# dashboard.net
KiCad netlist of a schematic drawn in EAGLE
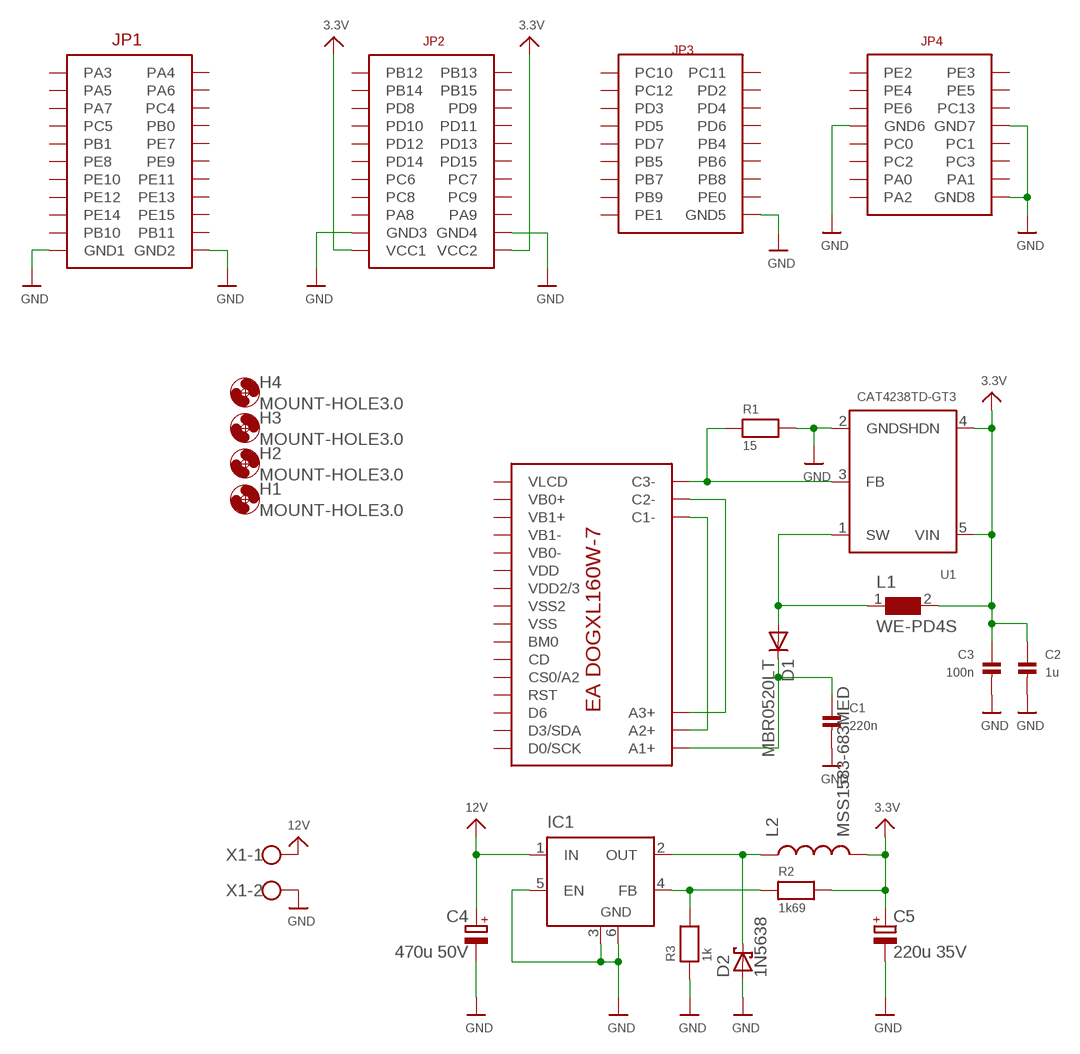
[diagram p0: schematic, sheet 1]

(export (version "E")
  (design (tool "Eeschema 10.0.6"))
  (components
    (comp (ref "C1")
      (value "220n")
      (footprint "eagle-import:_0805")
      (libsource (lib "eagle-import") (part "CAP_CERAMIC_0805"))
    )
    (comp (ref "C2")
      (value "1u")
      (footprint "eagle-import:_0805")
      (libsource (lib "eagle-import") (part "CAP_CERAMIC_0805"))
    )
    (comp (ref "C3")
      (value "100n")
      (footprint "eagle-import:_0603")
      (libsource (lib "eagle-import") (part "CAP_CERAMIC_0603"))
    )
    (comp (ref "C4")
      (value "470u 50V")
      (footprint "eagle-import:E5-13")
      (libsource (lib "eagle-import") (part "CPOL-EUE5-13"))
    )
    (comp (ref "C5")
      (value "220u 35V")
      (footprint "eagle-import:E3,5-8")
      (libsource (lib "eagle-import") (part "CPOL-EUE3.5-8"))
    )
    (comp (ref "D1")
      (value "MBR0520LT")
      (footprint "eagle-import:SOD123")
      (libsource (lib "eagle-import") (part "MBR0520LT"))
    )
    (comp (ref "D2")
      (value "1N5638")
      (footprint "eagle-import:DO13M")
      (libsource (lib "eagle-import") (part "1N5638"))
    )
    (comp (ref "H1")
      (value "MOUNT-HOLE3.0")
      (footprint "eagle-import:3,0")
      (libsource (lib "eagle-import") (part "MOUNT-HOLE3.0"))
    )
    (comp (ref "H2")
      (value "MOUNT-HOLE3.0")
      (footprint "eagle-import:3,0")
      (libsource (lib "eagle-import") (part "MOUNT-HOLE3.0"))
    )
    (comp (ref "H3")
      (value "MOUNT-HOLE3.0")
      (footprint "eagle-import:3,0")
      (libsource (lib "eagle-import") (part "MOUNT-HOLE3.0"))
    )
    (comp (ref "H4")
      (value "MOUNT-HOLE3.0")
      (footprint "eagle-import:3,0")
      (libsource (lib "eagle-import") (part "MOUNT-HOLE3.0"))
    )
    (comp (ref "IC1")
      (value "LM2596S")
      (footprint "eagle-import:TO263-5")
      (libsource (lib "eagle-import") (part "LM2596S"))
    )
    (comp (ref "L1")
      (value "WE-PD4S")
      (footprint "eagle-import:S")
      (fields (field (name "MPN") "7445501"))
      (libsource (lib "eagle-import") (part "WE-PD4_S-7445501"))
    )
    (comp (ref "L2")
      (value "MSS1583-683MED")
      (footprint "eagle-import:CDRH125")
      (libsource (lib "eagle-import") (part "INDUCTORPWR"))
    )
    (comp (ref "R1")
      (value "15")
      (footprint "eagle-import:_0603")
      (libsource (lib "eagle-import") (part "RESISTOR_0603"))
    )
    (comp (ref "R2")
      (value "1k69")
      (footprint "eagle-import:_0603")
      (libsource (lib "eagle-import") (part "RESISTOR_0603"))
    )
    (comp (ref "R3")
      (value "1k")
      (footprint "eagle-import:_0603")
      (libsource (lib "eagle-import") (part "RESISTOR_0603"))
    )
    (comp (ref "U$1")
      (value "CPU-BOARD")
      (footprint "eagle-import:CPU-BOARD-JP1")
      (libsource (lib "eagle-import") (part "CPU-BOARD"))
    )
    (comp (ref "U$10")
      (value "EA-DOGXL160W-7")
      (footprint "eagle-import:EA-DOGXL160W-7")
      (libsource (lib "eagle-import") (part "EA-DOGXL160W-7"))
    )
    (comp (ref "U1")
      (value "CAT4238TD-GT3")
      (footprint "eagle-import:SOT23-5")
      (libsource (lib "eagle-import") (part "FAN5331"))
    )
    (comp (ref "X1")
      (value "W237-102")
      (footprint "eagle-import:W237-102")
      (fields (field (name "MPN") "237-102"))
      (libsource (lib "eagle-import") (part "W237-102"))
    )
  )
  (nets
    (net (code "1") (name "3.3V") (class "Default")
      (node (ref "C2") (pin "1") (pinfunction "P$1_1") (pintype "passive"))
      (node (ref "C3") (pin "1") (pinfunction "P$1_1") (pintype "passive"))
      (node (ref "C5") (pin "+") (pinfunction "+_+") (pintype "passive"))
      (node (ref "L1") (pin "2") (pinfunction "2_2") (pintype "passive"))
      (node (ref "L2") (pin "2") (pinfunction "2_2") (pintype "passive"))
      (node (ref "R2") (pin "2") (pinfunction "2_2") (pintype "passive"))
      (node (ref "U$1") (pin "P$43") (pinfunction "VCC1_P$43") (pintype "bidirectional"))
      (node (ref "U$1") (pin "P$44") (pinfunction "VCC2_P$44") (pintype "bidirectional"))
      (node (ref "U1") (pin "4") (pinfunction "SHDN_4") (pintype "bidirectional"))
      (node (ref "U1") (pin "5") (pinfunction "VIN_5") (pintype "bidirectional"))
    )
    (net (code "2") (name "12V") (class "Default")
      (node (ref "C4") (pin "+") (pinfunction "+_+") (pintype "passive"))
      (node (ref "IC1") (pin "1") (pinfunction "IN_1") (pintype "input"))
      (node (ref "X1") (pin "1") (pinfunction "KL_1") (pintype "passive"))
    )
    (net (code "3") (name "GND") (class "Default")
      (node (ref "C1") (pin "2") (pinfunction "P$2_2") (pintype "passive"))
      (node (ref "C2") (pin "2") (pinfunction "P$2_2") (pintype "passive"))
      (node (ref "C3") (pin "2") (pinfunction "P$2_2") (pintype "passive"))
      (node (ref "C4") (pin "-") (pinfunction "-_-") (pintype "passive"))
      (node (ref "C5") (pin "-") (pinfunction "-_-") (pintype "passive"))
      (node (ref "D2") (pin "A") (pinfunction "A_A") (pintype "passive"))
      (node (ref "IC1") (pin "3") (pinfunction "GND_3") (pintype "power_in"))
      (node (ref "IC1") (pin "5") (pinfunction "EN_5") (pintype "input"))
      (node (ref "IC1") (pin "6") (pinfunction "GND_6") (pintype "power_in"))
      (node (ref "R1") (pin "2") (pinfunction "2_2") (pintype "passive"))
      (node (ref "R3") (pin "1") (pinfunction "1_1") (pintype "passive"))
      (node (ref "U$1") (pin "P$21") (pinfunction "GND1_P$21") (pintype "bidirectional"))
      (node (ref "U$1") (pin "P$22") (pinfunction "GND2_P$22") (pintype "bidirectional"))
      (node (ref "U$1") (pin "P$41") (pinfunction "GND3_P$41") (pintype "bidirectional"))
      (node (ref "U$1") (pin "P$42") (pinfunction "GND4_P$42") (pintype "bidirectional"))
      (node (ref "U$1") (pin "P$62") (pinfunction "GND5_P$62") (pintype "bidirectional"))
      (node (ref "U$1") (pin "P$69") (pinfunction "GND6_P$69") (pintype "bidirectional"))
      (node (ref "U$1") (pin "P$70") (pinfunction "GND7_P$70") (pintype "bidirectional"))
      (node (ref "U$1") (pin "P$78") (pinfunction "GND8_P$78") (pintype "bidirectional"))
      (node (ref "U1") (pin "2") (pinfunction "GND_2") (pintype "bidirectional"))
      (node (ref "X1") (pin "2") (pinfunction "KL_2") (pintype "passive"))
    )
    (net (code "4") (name "Net-(C1-P$1)") (class "Default")
      (node (ref "C1") (pin "1") (pinfunction "P$1_1") (pintype "passive"))
      (node (ref "D1") (pin "C") (pinfunction "C_C") (pintype "passive"))
      (node (ref "U$10") (pin "P$1") (pinfunction "A1+_P$1") (pintype "bidirectional"))
    )
    (net (code "5") (name "Net-(IC1-FB)") (class "Default")
      (node (ref "IC1") (pin "4") (pinfunction "FB_4") (pintype "input"))
      (node (ref "R2") (pin "1") (pinfunction "1_1") (pintype "passive"))
      (node (ref "R3") (pin "2") (pinfunction "2_2") (pintype "passive"))
    )
    (net (code "6") (name "Net-(IC1-OUT)") (class "Default")
      (node (ref "D2") (pin "C") (pinfunction "C_C") (pintype "passive"))
      (node (ref "IC1") (pin "2") (pinfunction "OUT_2") (pintype "output"))
      (node (ref "L2") (pin "1") (pinfunction "1_1") (pintype "passive"))
    )
    (net (code "7") (name "Net-(U$10-A2+)") (class "Default")
      (node (ref "U$10") (pin "P$14") (pinfunction "C1-_P$14") (pintype "bidirectional"))
      (node (ref "U$10") (pin "P$2") (pinfunction "A2+_P$2") (pintype "bidirectional"))
    )
    (net (code "8") (name "Net-(U$10-A3+)") (class "Default")
      (node (ref "U$10") (pin "P$15") (pinfunction "C2-_P$15") (pintype "bidirectional"))
      (node (ref "U$10") (pin "P$3") (pinfunction "A3+_P$3") (pintype "bidirectional"))
    )
    (net (code "9") (name "Net-(U$10-C3-)") (class "Default")
      (node (ref "R1") (pin "1") (pinfunction "1_1") (pintype "passive"))
      (node (ref "U$10") (pin "P$16") (pinfunction "C3-_P$16") (pintype "bidirectional"))
      (node (ref "U1") (pin "3") (pinfunction "FB_3") (pintype "bidirectional"))
    )
    (net (code "10") (name "Net-(U1-SW)") (class "Default")
      (node (ref "D1") (pin "A") (pinfunction "A_A") (pintype "passive"))
      (node (ref "L1") (pin "1") (pinfunction "1_1") (pintype "passive"))
      (node (ref "U1") (pin "1") (pinfunction "SW_1") (pintype "bidirectional"))
    )
    (net (code "11") (name "unconnected-(U$1A-PA3-PadP$1)") (class "Default")
      (node (ref "U$1") (pin "P$1") (pinfunction "PA3_P$1") (pintype "bidirectional"))
    )
    (net (code "12") (name "unconnected-(U$1A-PA4-PadP$2)") (class "Default")
      (node (ref "U$1") (pin "P$2") (pinfunction "PA4_P$2") (pintype "bidirectional"))
    )
    (net (code "13") (name "unconnected-(U$1A-PA5-PadP$3)") (class "Default")
      (node (ref "U$1") (pin "P$3") (pinfunction "PA5_P$3") (pintype "bidirectional"))
    )
    (net (code "14") (name "unconnected-(U$1A-PA6-PadP$4)") (class "Default")
      (node (ref "U$1") (pin "P$4") (pinfunction "PA6_P$4") (pintype "bidirectional"))
    )
    (net (code "15") (name "unconnected-(U$1A-PA7-PadP$5)") (class "Default")
      (node (ref "U$1") (pin "P$5") (pinfunction "PA7_P$5") (pintype "bidirectional"))
    )
    (net (code "16") (name "unconnected-(U$1A-PB0-PadP$8)") (class "Default")
      (node (ref "U$1") (pin "P$8") (pinfunction "PB0_P$8") (pintype "bidirectional"))
    )
    (net (code "17") (name "unconnected-(U$1A-PB1-PadP$9)") (class "Default")
      (node (ref "U$1") (pin "P$9") (pinfunction "PB1_P$9") (pintype "bidirectional"))
    )
    (net (code "18") (name "unconnected-(U$1A-PB10-PadP$19)") (class "Default")
      (node (ref "U$1") (pin "P$19") (pinfunction "PB10_P$19") (pintype "bidirectional"))
    )
    (net (code "19") (name "unconnected-(U$1A-PB11-PadP$20)") (class "Default")
      (node (ref "U$1") (pin "P$20") (pinfunction "PB11_P$20") (pintype "bidirectional"))
    )
    (net (code "20") (name "unconnected-(U$1A-PC4-PadP$6)") (class "Default")
      (node (ref "U$1") (pin "P$6") (pinfunction "PC4_P$6") (pintype "bidirectional"))
    )
    (net (code "21") (name "unconnected-(U$1A-PC5-PadP$7)") (class "Default")
      (node (ref "U$1") (pin "P$7") (pinfunction "PC5_P$7") (pintype "bidirectional"))
    )
    (net (code "22") (name "unconnected-(U$1A-PE7-PadP$10)") (class "Default")
      (node (ref "U$1") (pin "P$10") (pinfunction "PE7_P$10") (pintype "bidirectional"))
    )
    (net (code "23") (name "unconnected-(U$1A-PE8-PadP$11)") (class "Default")
      (node (ref "U$1") (pin "P$11") (pinfunction "PE8_P$11") (pintype "bidirectional"))
    )
    (net (code "24") (name "unconnected-(U$1A-PE9-PadP$12)") (class "Default")
      (node (ref "U$1") (pin "P$12") (pinfunction "PE9_P$12") (pintype "bidirectional"))
    )
    (net (code "25") (name "unconnected-(U$1A-PE10-PadP$13)") (class "Default")
      (node (ref "U$1") (pin "P$13") (pinfunction "PE10_P$13") (pintype "bidirectional"))
    )
    (net (code "26") (name "unconnected-(U$1A-PE11-PadP$14)") (class "Default")
      (node (ref "U$1") (pin "P$14") (pinfunction "PE11_P$14") (pintype "bidirectional"))
    )
    (net (code "27") (name "unconnected-(U$1A-PE12-PadP$15)") (class "Default")
      (node (ref "U$1") (pin "P$15") (pinfunction "PE12_P$15") (pintype "bidirectional"))
    )
    (net (code "28") (name "unconnected-(U$1A-PE13-PadP$16)") (class "Default")
      (node (ref "U$1") (pin "P$16") (pinfunction "PE13_P$16") (pintype "bidirectional"))
    )
    (net (code "29") (name "unconnected-(U$1A-PE14-PadP$17)") (class "Default")
      (node (ref "U$1") (pin "P$17") (pinfunction "PE14_P$17") (pintype "bidirectional"))
    )
    (net (code "30") (name "unconnected-(U$1A-PE15-PadP$18)") (class "Default")
      (node (ref "U$1") (pin "P$18") (pinfunction "PE15_P$18") (pintype "bidirectional"))
    )
    (net (code "31") (name "unconnected-(U$1B-PA8-PadP$39)") (class "Default")
      (node (ref "U$1") (pin "P$39") (pinfunction "PA8_P$39") (pintype "bidirectional"))
    )
    (net (code "32") (name "unconnected-(U$1B-PA9-PadP$40)") (class "Default")
      (node (ref "U$1") (pin "P$40") (pinfunction "PA9_P$40") (pintype "bidirectional"))
    )
    (net (code "33") (name "unconnected-(U$1B-PB12-PadP$23)") (class "Default")
      (node (ref "U$1") (pin "P$23") (pinfunction "PB12_P$23") (pintype "bidirectional"))
    )
    (net (code "34") (name "unconnected-(U$1B-PB13-PadP$24)") (class "Default")
      (node (ref "U$1") (pin "P$24") (pinfunction "PB13_P$24") (pintype "bidirectional"))
    )
    (net (code "35") (name "unconnected-(U$1B-PB14-PadP$25)") (class "Default")
      (node (ref "U$1") (pin "P$25") (pinfunction "PB14_P$25") (pintype "bidirectional"))
    )
    (net (code "36") (name "unconnected-(U$1B-PB15-PadP$26)") (class "Default")
      (node (ref "U$1") (pin "P$26") (pinfunction "PB15_P$26") (pintype "bidirectional"))
    )
    (net (code "37") (name "unconnected-(U$1B-PC6-PadP$35)") (class "Default")
      (node (ref "U$1") (pin "P$35") (pinfunction "PC6_P$35") (pintype "bidirectional"))
    )
    (net (code "38") (name "unconnected-(U$1B-PC7-PadP$36)") (class "Default")
      (node (ref "U$1") (pin "P$36") (pinfunction "PC7_P$36") (pintype "bidirectional"))
    )
    (net (code "39") (name "unconnected-(U$1B-PC8-PadP$37)") (class "Default")
      (node (ref "U$1") (pin "P$37") (pinfunction "PC8_P$37") (pintype "bidirectional"))
    )
    (net (code "40") (name "unconnected-(U$1B-PC9-PadP$38)") (class "Default")
      (node (ref "U$1") (pin "P$38") (pinfunction "PC9_P$38") (pintype "bidirectional"))
    )
    (net (code "41") (name "unconnected-(U$1B-PD8-PadP$27)") (class "Default")
      (node (ref "U$1") (pin "P$27") (pinfunction "PD8_P$27") (pintype "bidirectional"))
    )
    (net (code "42") (name "unconnected-(U$1B-PD9-PadP$28)") (class "Default")
      (node (ref "U$1") (pin "P$28") (pinfunction "PD9_P$28") (pintype "bidirectional"))
    )
    (net (code "43") (name "unconnected-(U$1B-PD10-PadP$29)") (class "Default")
      (node (ref "U$1") (pin "P$29") (pinfunction "PD10_P$29") (pintype "bidirectional"))
    )
    (net (code "44") (name "unconnected-(U$1B-PD11-PadP$30)") (class "Default")
      (node (ref "U$1") (pin "P$30") (pinfunction "PD11_P$30") (pintype "bidirectional"))
    )
    (net (code "45") (name "unconnected-(U$1B-PD12-PadP$31)") (class "Default")
      (node (ref "U$1") (pin "P$31") (pinfunction "PD12_P$31") (pintype "bidirectional"))
    )
    (net (code "46") (name "unconnected-(U$1B-PD13-PadP$32)") (class "Default")
      (node (ref "U$1") (pin "P$32") (pinfunction "PD13_P$32") (pintype "bidirectional"))
    )
    (net (code "47") (name "unconnected-(U$1B-PD14-PadP$33)") (class "Default")
      (node (ref "U$1") (pin "P$33") (pinfunction "PD14_P$33") (pintype "bidirectional"))
    )
    (net (code "48") (name "unconnected-(U$1B-PD15-PadP$34)") (class "Default")
      (node (ref "U$1") (pin "P$34") (pinfunction "PD15_P$34") (pintype "bidirectional"))
    )
    (net (code "49") (name "unconnected-(U$1C-PB4-PadP$54)") (class "Default")
      (node (ref "U$1") (pin "P$54") (pinfunction "PB4_P$54") (pintype "bidirectional"))
    )
    (net (code "50") (name "unconnected-(U$1C-PB5-PadP$55)") (class "Default")
      (node (ref "U$1") (pin "P$55") (pinfunction "PB5_P$55") (pintype "bidirectional"))
    )
    (net (code "51") (name "unconnected-(U$1C-PB6-PadP$56)") (class "Default")
      (node (ref "U$1") (pin "P$56") (pinfunction "PB6_P$56") (pintype "bidirectional"))
    )
    (net (code "52") (name "unconnected-(U$1C-PB7-PadP$57)") (class "Default")
      (node (ref "U$1") (pin "P$57") (pinfunction "PB7_P$57") (pintype "bidirectional"))
    )
    (net (code "53") (name "unconnected-(U$1C-PB8-PadP$58)") (class "Default")
      (node (ref "U$1") (pin "P$58") (pinfunction "PB8_P$58") (pintype "bidirectional"))
    )
    (net (code "54") (name "unconnected-(U$1C-PB9-PadP$59)") (class "Default")
      (node (ref "U$1") (pin "P$59") (pinfunction "PB9_P$59") (pintype "bidirectional"))
    )
    (net (code "55") (name "unconnected-(U$1C-PC10-PadP$45)") (class "Default")
      (node (ref "U$1") (pin "P$45") (pinfunction "PC10_P$45") (pintype "bidirectional"))
    )
    (net (code "56") (name "unconnected-(U$1C-PC11-PadP$46)") (class "Default")
      (node (ref "U$1") (pin "P$46") (pinfunction "PC11_P$46") (pintype "bidirectional"))
    )
    (net (code "57") (name "unconnected-(U$1C-PC12-PadP$47)") (class "Default")
      (node (ref "U$1") (pin "P$47") (pinfunction "PC12_P$47") (pintype "bidirectional"))
    )
    (net (code "58") (name "unconnected-(U$1C-PD2-PadP$48)") (class "Default")
      (node (ref "U$1") (pin "P$48") (pinfunction "PD2_P$48") (pintype "bidirectional"))
    )
    (net (code "59") (name "unconnected-(U$1C-PD3-PadP$49)") (class "Default")
      (node (ref "U$1") (pin "P$49") (pinfunction "PD3_P$49") (pintype "bidirectional"))
    )
    (net (code "60") (name "unconnected-(U$1C-PD4-PadP$50)") (class "Default")
      (node (ref "U$1") (pin "P$50") (pinfunction "PD4_P$50") (pintype "bidirectional"))
    )
    (net (code "61") (name "unconnected-(U$1C-PD5-PadP$51)") (class "Default")
      (node (ref "U$1") (pin "P$51") (pinfunction "PD5_P$51") (pintype "bidirectional"))
    )
    (net (code "62") (name "unconnected-(U$1C-PD6-PadP$52)") (class "Default")
      (node (ref "U$1") (pin "P$52") (pinfunction "PD6_P$52") (pintype "bidirectional"))
    )
    (net (code "63") (name "unconnected-(U$1C-PD7-PadP$53)") (class "Default")
      (node (ref "U$1") (pin "P$53") (pinfunction "PD7_P$53") (pintype "bidirectional"))
    )
    (net (code "64") (name "unconnected-(U$1C-PE0-PadP$60)") (class "Default")
      (node (ref "U$1") (pin "P$60") (pinfunction "PE0_P$60") (pintype "bidirectional"))
    )
    (net (code "65") (name "unconnected-(U$1C-PE1-PadP$61)") (class "Default")
      (node (ref "U$1") (pin "P$61") (pinfunction "PE1_P$61") (pintype "bidirectional"))
    )
    (net (code "66") (name "unconnected-(U$1D-PA0-PadP$75)") (class "Default")
      (node (ref "U$1") (pin "P$75") (pinfunction "PA0_P$75") (pintype "bidirectional"))
    )
    (net (code "67") (name "unconnected-(U$1D-PA1-PadP$76)") (class "Default")
      (node (ref "U$1") (pin "P$76") (pinfunction "PA1_P$76") (pintype "bidirectional"))
    )
    (net (code "68") (name "unconnected-(U$1D-PA2-PadP$77)") (class "Default")
      (node (ref "U$1") (pin "P$77") (pinfunction "PA2_P$77") (pintype "bidirectional"))
    )
    (net (code "69") (name "unconnected-(U$1D-PC0-PadP$71)") (class "Default")
      (node (ref "U$1") (pin "P$71") (pinfunction "PC0_P$71") (pintype "bidirectional"))
    )
    (net (code "70") (name "unconnected-(U$1D-PC1-PadP$72)") (class "Default")
      (node (ref "U$1") (pin "P$72") (pinfunction "PC1_P$72") (pintype "bidirectional"))
    )
    (net (code "71") (name "unconnected-(U$1D-PC2-PadP$73)") (class "Default")
      (node (ref "U$1") (pin "P$73") (pinfunction "PC2_P$73") (pintype "bidirectional"))
    )
    (net (code "72") (name "unconnected-(U$1D-PC3-PadP$74)") (class "Default")
      (node (ref "U$1") (pin "P$74") (pinfunction "PC3_P$74") (pintype "bidirectional"))
    )
    (net (code "73") (name "unconnected-(U$1D-PC13-PadP$68)") (class "Default")
      (node (ref "U$1") (pin "P$68") (pinfunction "PC13_P$68") (pintype "bidirectional"))
    )
    (net (code "74") (name "unconnected-(U$1D-PE2-PadP$63)") (class "Default")
      (node (ref "U$1") (pin "P$63") (pinfunction "PE2_P$63") (pintype "bidirectional"))
    )
    (net (code "75") (name "unconnected-(U$1D-PE3-PadP$64)") (class "Default")
      (node (ref "U$1") (pin "P$64") (pinfunction "PE3_P$64") (pintype "bidirectional"))
    )
    (net (code "76") (name "unconnected-(U$1D-PE4-PadP$65)") (class "Default")
      (node (ref "U$1") (pin "P$65") (pinfunction "PE4_P$65") (pintype "bidirectional"))
    )
    (net (code "77") (name "unconnected-(U$1D-PE5-PadP$66)") (class "Default")
      (node (ref "U$1") (pin "P$66") (pinfunction "PE5_P$66") (pintype "bidirectional"))
    )
    (net (code "78") (name "unconnected-(U$1D-PE6-PadP$67)") (class "Default")
      (node (ref "U$1") (pin "P$67") (pinfunction "PE6_P$67") (pintype "bidirectional"))
    )
    (net (code "79") (name "unconnected-(U$10-BM0-PadP$26)") (class "Default")
      (node (ref "U$10") (pin "P$26") (pinfunction "BM0_P$26") (pintype "bidirectional"))
    )
    (net (code "80") (name "unconnected-(U$10-CD-PadP$27)") (class "Default")
      (node (ref "U$10") (pin "P$27") (pinfunction "CD_P$27") (pintype "bidirectional"))
    )
    (net (code "81") (name "unconnected-(U$10-CS0{slash}A2-PadP$28)") (class "Default")
      (node (ref "U$10") (pin "P$28") (pinfunction "CS0/A2_P$28") (pintype "bidirectional"))
    )
    (net (code "82") (name "unconnected-(U$10-D0{slash}SCK-PadP$32)") (class "Default")
      (node (ref "U$10") (pin "P$32") (pinfunction "D0/SCK_P$32") (pintype "bidirectional"))
    )
    (net (code "83") (name "unconnected-(U$10-D3{slash}SDA-PadP$31)") (class "Default")
      (node (ref "U$10") (pin "P$31") (pinfunction "D3/SDA_P$31") (pintype "bidirectional"))
    )
    (net (code "84") (name "unconnected-(U$10-D6-PadP$30)") (class "Default")
      (node (ref "U$10") (pin "P$30") (pinfunction "D6_P$30") (pintype "bidirectional"))
    )
    (net (code "85") (name "unconnected-(U$10-RST-PadP$29)") (class "Default")
      (node (ref "U$10") (pin "P$29") (pinfunction "RST_P$29") (pintype "bidirectional"))
    )
    (net (code "86") (name "unconnected-(U$10-VB0+-PadP$18)") (class "Default")
      (node (ref "U$10") (pin "P$18") (pinfunction "VB0+_P$18") (pintype "bidirectional"))
    )
    (net (code "87") (name "unconnected-(U$10-VB0--PadP$21)") (class "Default")
      (node (ref "U$10") (pin "P$21") (pinfunction "VB0-_P$21") (pintype "bidirectional"))
    )
    (net (code "88") (name "unconnected-(U$10-VB1+-PadP$19)") (class "Default")
      (node (ref "U$10") (pin "P$19") (pinfunction "VB1+_P$19") (pintype "bidirectional"))
    )
    (net (code "89") (name "unconnected-(U$10-VB1--PadP$20)") (class "Default")
      (node (ref "U$10") (pin "P$20") (pinfunction "VB1-_P$20") (pintype "bidirectional"))
    )
    (net (code "90") (name "unconnected-(U$10-VDD-PadP$22)") (class "Default")
      (node (ref "U$10") (pin "P$22") (pinfunction "VDD_P$22") (pintype "bidirectional"))
    )
    (net (code "91") (name "unconnected-(U$10-VDD2{slash}3-PadP$23)") (class "Default")
      (node (ref "U$10") (pin "P$23") (pinfunction "VDD2/3_P$23") (pintype "bidirectional"))
    )
    (net (code "92") (name "unconnected-(U$10-VLCD-PadP$17)") (class "Default")
      (node (ref "U$10") (pin "P$17") (pinfunction "VLCD_P$17") (pintype "bidirectional"))
    )
    (net (code "93") (name "unconnected-(U$10-VSS-PadP$25)") (class "Default")
      (node (ref "U$10") (pin "P$25") (pinfunction "VSS_P$25") (pintype "bidirectional"))
    )
    (net (code "94") (name "unconnected-(U$10-VSS2-PadP$24)") (class "Default")
      (node (ref "U$10") (pin "P$24") (pinfunction "VSS2_P$24") (pintype "bidirectional"))
    )
  )
)
